# BPW5015-16bitBuffer.net
KiCad netlist of a schematic drawn in EAGLE
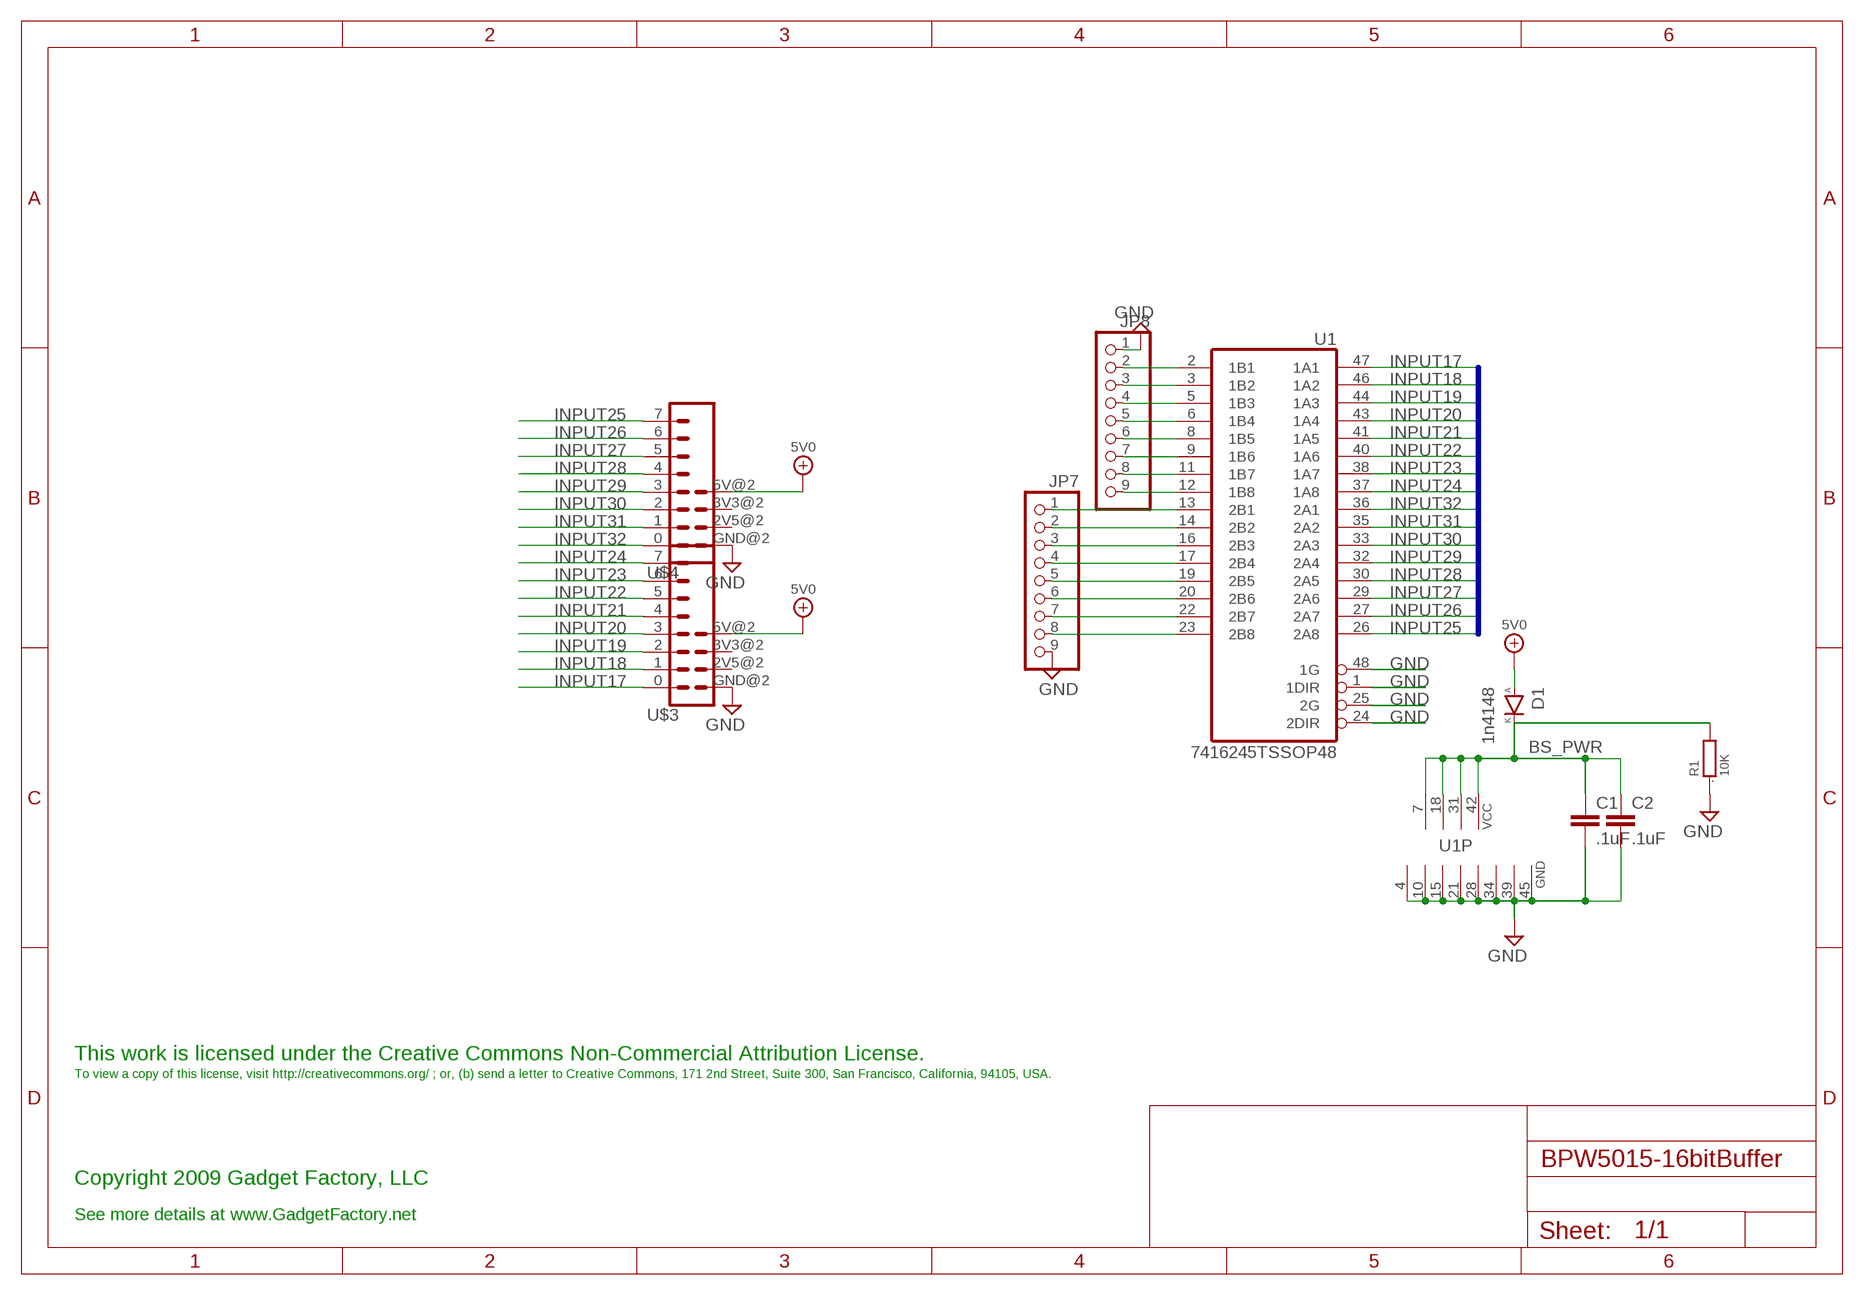
[diagram p0: schematic, sheet 1]

(export (version "E")
  (design (tool "Eeschema 10.0.6"))
  (components
    (comp (ref "C1")
      (value ".1uF")
      (footprint "eagle-import:C0603")
      (libsource (lib "eagle-import") (part "C-EUC0603"))
    )
    (comp (ref "C2")
      (value ".1uF")
      (footprint "eagle-import:C0603")
      (libsource (lib "eagle-import") (part "C-EUC0603"))
    )
    (comp (ref "D1")
      (value "1n4148")
      (footprint "eagle-import:SOD323")
      (libsource (lib "eagle-import") (part "DIODE_SOD323"))
    )
    (comp (ref "JP7")
      (value "PINHD-1X9")
      (footprint "eagle-import:1X09")
      (libsource (lib "eagle-import") (part "PINHD-1X9"))
    )
    (comp (ref "JP8")
      (value "PINHD-1X9")
      (footprint "eagle-import:1X09")
      (libsource (lib "eagle-import") (part "PINHD-1X9"))
    )
    (comp (ref "R1")
      (value "10K")
      (footprint "eagle-import:0603")
      (libsource (lib "eagle-import") (part "R0603"))
    )
    (comp (ref "U$3")
      (value "WING8")
      (footprint "eagle-import:WINGSIDE_8BIT")
      (libsource (lib "eagle-import") (part "WING8"))
    )
    (comp (ref "U$4")
      (value "WING8")
      (footprint "eagle-import:WINGSIDE_8BIT")
      (libsource (lib "eagle-import") (part "WING8"))
    )
    (comp (ref "U1")
      (value "7416245TSSOP48")
      (footprint "eagle-import:TSSOP48")
      (libsource (lib "eagle-import") (part "7416245TSSOP48"))
    )
  )
  (nets
    (net (code "1") (name "/BS_PWR") (class "Default")
      (node (ref "C1") (pin "1") (pinfunction "1_1") (pintype "passive"))
      (node (ref "C2") (pin "1") (pinfunction "1_1") (pintype "passive"))
      (node (ref "D1") (pin "K") (pinfunction "K_K") (pintype "passive"))
      (node (ref "R1") (pin "2") (pinfunction "2_2") (pintype "passive"))
      (node (ref "U1") (pin "18") (pinfunction "VCC_18") (pintype "power_in"))
      (node (ref "U1") (pin "31") (pinfunction "VCC_31") (pintype "power_in"))
      (node (ref "U1") (pin "42") (pinfunction "VCC_42") (pintype "power_in"))
      (node (ref "U1") (pin "7") (pinfunction "VCC_7") (pintype "power_in"))
    )
    (net (code "2") (name "/INPUT17") (class "Default")
      (node (ref "U$3") (pin "0") (pinfunction "1_0") (pintype "passive"))
      (node (ref "U1") (pin "47") (pinfunction "1A1_47") (pintype "bidirectional"))
    )
    (net (code "3") (name "/INPUT18") (class "Default")
      (node (ref "U$3") (pin "1") (pinfunction "2_1") (pintype "passive"))
      (node (ref "U1") (pin "46") (pinfunction "1A2_46") (pintype "bidirectional"))
    )
    (net (code "4") (name "/INPUT19") (class "Default")
      (node (ref "U$3") (pin "2") (pinfunction "3_2") (pintype "passive"))
      (node (ref "U1") (pin "44") (pinfunction "1A3_44") (pintype "bidirectional"))
    )
    (net (code "5") (name "/INPUT20") (class "Default")
      (node (ref "U$3") (pin "3") (pinfunction "4_3") (pintype "passive"))
      (node (ref "U1") (pin "43") (pinfunction "1A4_43") (pintype "bidirectional"))
    )
    (net (code "6") (name "/INPUT21") (class "Default")
      (node (ref "U$3") (pin "4") (pinfunction "5_4") (pintype "passive"))
      (node (ref "U1") (pin "41") (pinfunction "1A5_41") (pintype "bidirectional"))
    )
    (net (code "7") (name "/INPUT22") (class "Default")
      (node (ref "U$3") (pin "5") (pinfunction "6_5") (pintype "passive"))
      (node (ref "U1") (pin "40") (pinfunction "1A6_40") (pintype "bidirectional"))
    )
    (net (code "8") (name "/INPUT23") (class "Default")
      (node (ref "U$3") (pin "6") (pinfunction "7_6") (pintype "passive"))
      (node (ref "U1") (pin "38") (pinfunction "1A7_38") (pintype "bidirectional"))
    )
    (net (code "9") (name "/INPUT24") (class "Default")
      (node (ref "U$3") (pin "7") (pinfunction "8_7") (pintype "passive"))
      (node (ref "U1") (pin "37") (pinfunction "1A8_37") (pintype "bidirectional"))
    )
    (net (code "10") (name "/INPUT25") (class "Default")
      (node (ref "U$4") (pin "7") (pinfunction "8_7") (pintype "passive"))
      (node (ref "U1") (pin "26") (pinfunction "2A8_26") (pintype "bidirectional"))
    )
    (net (code "11") (name "/INPUT26") (class "Default")
      (node (ref "U$4") (pin "6") (pinfunction "7_6") (pintype "passive"))
      (node (ref "U1") (pin "27") (pinfunction "2A7_27") (pintype "bidirectional"))
    )
    (net (code "12") (name "/INPUT27") (class "Default")
      (node (ref "U$4") (pin "5") (pinfunction "6_5") (pintype "passive"))
      (node (ref "U1") (pin "29") (pinfunction "2A6_29") (pintype "bidirectional"))
    )
    (net (code "13") (name "/INPUT28") (class "Default")
      (node (ref "U$4") (pin "4") (pinfunction "5_4") (pintype "passive"))
      (node (ref "U1") (pin "30") (pinfunction "2A5_30") (pintype "bidirectional"))
    )
    (net (code "14") (name "/INPUT29") (class "Default")
      (node (ref "U$4") (pin "3") (pinfunction "4_3") (pintype "passive"))
      (node (ref "U1") (pin "32") (pinfunction "2A4_32") (pintype "bidirectional"))
    )
    (net (code "15") (name "/INPUT30") (class "Default")
      (node (ref "U$4") (pin "2") (pinfunction "3_2") (pintype "passive"))
      (node (ref "U1") (pin "33") (pinfunction "2A3_33") (pintype "bidirectional"))
    )
    (net (code "16") (name "/INPUT31") (class "Default")
      (node (ref "U$4") (pin "1") (pinfunction "2_1") (pintype "passive"))
      (node (ref "U1") (pin "35") (pinfunction "2A2_35") (pintype "bidirectional"))
    )
    (net (code "17") (name "/INPUT32") (class "Default")
      (node (ref "U$4") (pin "0") (pinfunction "1_0") (pintype "passive"))
      (node (ref "U1") (pin "36") (pinfunction "2A1_36") (pintype "bidirectional"))
    )
    (net (code "18") (name "5V0") (class "Default")
      (node (ref "D1") (pin "A") (pinfunction "A_A") (pintype "passive"))
      (node (ref "U$3") (pin "5V@2") (pinfunction "5V_5V@2") (pintype "passive"))
      (node (ref "U$4") (pin "5V@2") (pinfunction "5V_5V@2") (pintype "passive"))
    )
    (net (code "19") (name "GND") (class "Default")
      (node (ref "C1") (pin "2") (pinfunction "2_2") (pintype "passive"))
      (node (ref "C2") (pin "2") (pinfunction "2_2") (pintype "passive"))
      (node (ref "JP7") (pin "9") (pinfunction "9_9") (pintype "passive"))
      (node (ref "JP8") (pin "1") (pinfunction "1_1") (pintype "passive"))
      (node (ref "R1") (pin "1") (pinfunction "1_1") (pintype "passive"))
      (node (ref "U$3") (pin "GND@2") (pinfunction "GND_GND@2") (pintype "passive"))
      (node (ref "U$4") (pin "GND@2") (pinfunction "GND_GND@2") (pintype "passive"))
      (node (ref "U1") (pin "1") (pinfunction "1DIR_1") (pintype "input"))
      (node (ref "U1") (pin "10") (pinfunction "GND_10") (pintype "power_in"))
      (node (ref "U1") (pin "15") (pinfunction "GND_15") (pintype "power_in"))
      (node (ref "U1") (pin "21") (pinfunction "GND_21") (pintype "power_in"))
      (node (ref "U1") (pin "24") (pinfunction "2DIR_24") (pintype "input"))
      (node (ref "U1") (pin "25") (pinfunction "2G_25") (pintype "input"))
      (node (ref "U1") (pin "28") (pinfunction "GND_28") (pintype "power_in"))
      (node (ref "U1") (pin "34") (pinfunction "GND_34") (pintype "power_in"))
      (node (ref "U1") (pin "39") (pinfunction "GND_39") (pintype "power_in"))
      (node (ref "U1") (pin "4") (pinfunction "GND_4") (pintype "power_in"))
      (node (ref "U1") (pin "45") (pinfunction "GND_45") (pintype "power_in"))
      (node (ref "U1") (pin "48") (pinfunction "1G_48") (pintype "input"))
    )
    (net (code "20") (name "Net-(U1A-1B1)") (class "Default")
      (node (ref "JP8") (pin "2") (pinfunction "2_2") (pintype "passive"))
      (node (ref "U1") (pin "2") (pinfunction "1B1_2") (pintype "bidirectional"))
    )
    (net (code "21") (name "Net-(U1A-1B2)") (class "Default")
      (node (ref "JP8") (pin "3") (pinfunction "3_3") (pintype "passive"))
      (node (ref "U1") (pin "3") (pinfunction "1B2_3") (pintype "bidirectional"))
    )
    (net (code "22") (name "Net-(U1A-1B3)") (class "Default")
      (node (ref "JP8") (pin "4") (pinfunction "4_4") (pintype "passive"))
      (node (ref "U1") (pin "5") (pinfunction "1B3_5") (pintype "bidirectional"))
    )
    (net (code "23") (name "Net-(U1A-1B4)") (class "Default")
      (node (ref "JP8") (pin "5") (pinfunction "5_5") (pintype "passive"))
      (node (ref "U1") (pin "6") (pinfunction "1B4_6") (pintype "bidirectional"))
    )
    (net (code "24") (name "Net-(U1A-1B5)") (class "Default")
      (node (ref "JP8") (pin "6") (pinfunction "6_6") (pintype "passive"))
      (node (ref "U1") (pin "8") (pinfunction "1B5_8") (pintype "bidirectional"))
    )
    (net (code "25") (name "Net-(U1A-1B6)") (class "Default")
      (node (ref "JP8") (pin "7") (pinfunction "7_7") (pintype "passive"))
      (node (ref "U1") (pin "9") (pinfunction "1B6_9") (pintype "bidirectional"))
    )
    (net (code "26") (name "Net-(U1A-1B7)") (class "Default")
      (node (ref "JP8") (pin "8") (pinfunction "8_8") (pintype "passive"))
      (node (ref "U1") (pin "11") (pinfunction "1B7_11") (pintype "bidirectional"))
    )
    (net (code "27") (name "Net-(U1A-1B8)") (class "Default")
      (node (ref "JP8") (pin "9") (pinfunction "9_9") (pintype "passive"))
      (node (ref "U1") (pin "12") (pinfunction "1B8_12") (pintype "bidirectional"))
    )
    (net (code "28") (name "Net-(U1A-2B1)") (class "Default")
      (node (ref "JP7") (pin "1") (pinfunction "1_1") (pintype "passive"))
      (node (ref "U1") (pin "13") (pinfunction "2B1_13") (pintype "bidirectional"))
    )
    (net (code "29") (name "Net-(U1A-2B2)") (class "Default")
      (node (ref "JP7") (pin "2") (pinfunction "2_2") (pintype "passive"))
      (node (ref "U1") (pin "14") (pinfunction "2B2_14") (pintype "bidirectional"))
    )
    (net (code "30") (name "Net-(U1A-2B3)") (class "Default")
      (node (ref "JP7") (pin "3") (pinfunction "3_3") (pintype "passive"))
      (node (ref "U1") (pin "16") (pinfunction "2B3_16") (pintype "bidirectional"))
    )
    (net (code "31") (name "Net-(U1A-2B4)") (class "Default")
      (node (ref "JP7") (pin "4") (pinfunction "4_4") (pintype "passive"))
      (node (ref "U1") (pin "17") (pinfunction "2B4_17") (pintype "bidirectional"))
    )
    (net (code "32") (name "Net-(U1A-2B5)") (class "Default")
      (node (ref "JP7") (pin "5") (pinfunction "5_5") (pintype "passive"))
      (node (ref "U1") (pin "19") (pinfunction "2B5_19") (pintype "bidirectional"))
    )
    (net (code "33") (name "Net-(U1A-2B6)") (class "Default")
      (node (ref "JP7") (pin "6") (pinfunction "6_6") (pintype "passive"))
      (node (ref "U1") (pin "20") (pinfunction "2B6_20") (pintype "bidirectional"))
    )
    (net (code "34") (name "Net-(U1A-2B7)") (class "Default")
      (node (ref "JP7") (pin "7") (pinfunction "7_7") (pintype "passive"))
      (node (ref "U1") (pin "22") (pinfunction "2B7_22") (pintype "bidirectional"))
    )
    (net (code "35") (name "Net-(U1A-2B8)") (class "Default")
      (node (ref "JP7") (pin "8") (pinfunction "8_8") (pintype "passive"))
      (node (ref "U1") (pin "23") (pinfunction "2B8_23") (pintype "bidirectional"))
    )
    (net (code "36") (name "unconnected-(U$3-2V5-Pad2V5@2)") (class "Default")
      (node (ref "U$3") (pin "2V5@2") (pinfunction "2V5_2V5@2") (pintype "passive"))
    )
    (net (code "37") (name "unconnected-(U$3-3V3-Pad3V3@2)") (class "Default")
      (node (ref "U$3") (pin "3V3@2") (pinfunction "3V3_3V3@2") (pintype "passive"))
    )
    (net (code "38") (name "unconnected-(U$4-2V5-Pad2V5@2)") (class "Default")
      (node (ref "U$4") (pin "2V5@2") (pinfunction "2V5_2V5@2") (pintype "passive"))
    )
    (net (code "39") (name "unconnected-(U$4-3V3-Pad3V3@2)") (class "Default")
      (node (ref "U$4") (pin "3V3@2") (pinfunction "3V3_3V3@2") (pintype "passive"))
    )
  )
)
